# MD_20w.net
KiCad netlist of a schematic drawn in EAGLE
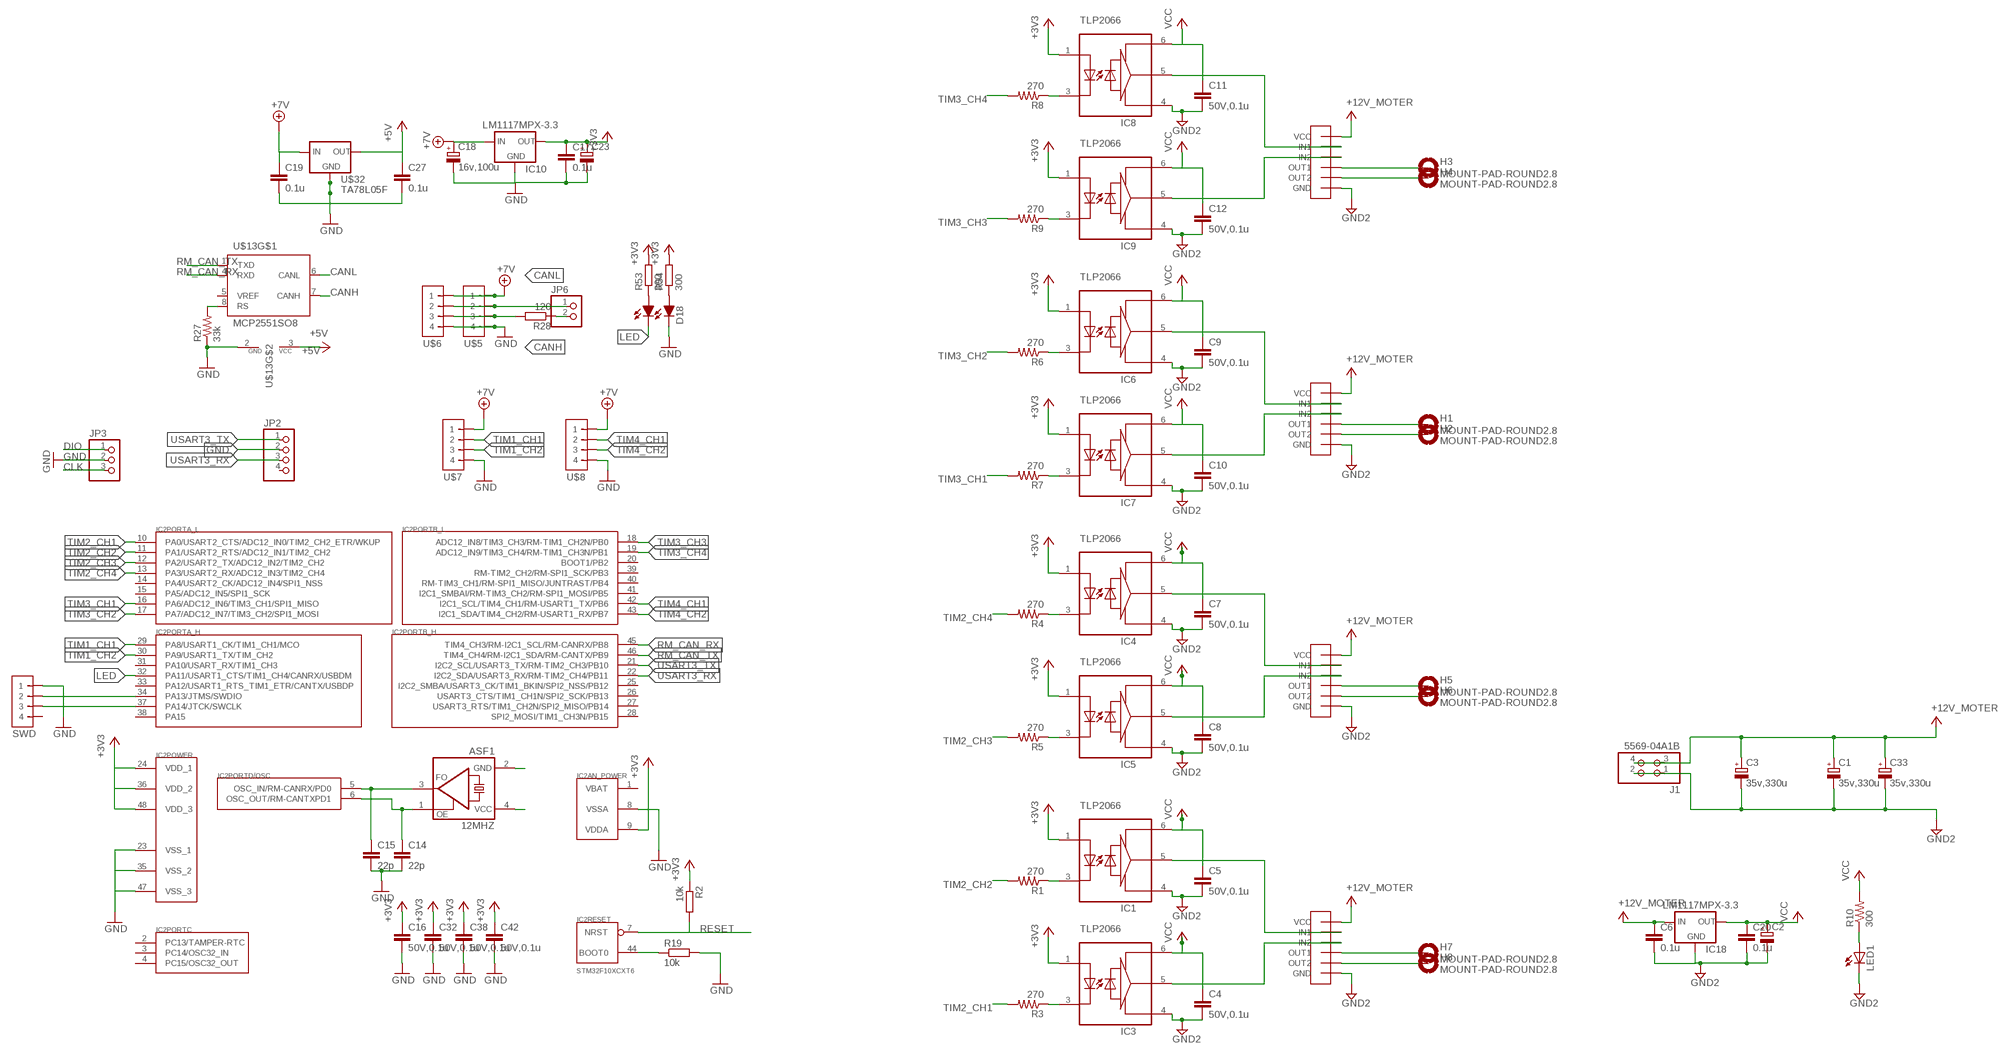
[diagram p0: schematic, sheet 1]

(export (version "E")
  (design (tool "Eeschema 10.0.6"))
  (components
    (comp (ref "12MHZ")
      (value "ASF1")
      (footprint "eagle-import:ASF")
      (libsource (lib "eagle-import") (part "ASF1"))
    )
    (comp (ref "C1")
      (value "35v,330u")
      (footprint "eagle-import:153CLV-1010")
      (libsource (lib "eagle-import") (part "CPOL-EU153CLV-1010"))
    )
    (comp (ref "C2")
      (value "CPOL-EU153CLV-0505")
      (footprint "eagle-import:153CLV-0505")
      (libsource (lib "eagle-import") (part "CPOL-EU153CLV-0505"))
    )
    (comp (ref "C3")
      (value "35v,330u")
      (footprint "eagle-import:153CLV-1010")
      (libsource (lib "eagle-import") (part "CPOL-EU153CLV-1010"))
    )
    (comp (ref "C4")
      (value "50V,0.1u")
      (footprint "eagle-import:C0603")
      (libsource (lib "eagle-import") (part "C-EUC0603"))
    )
    (comp (ref "C5")
      (value "50V,0.1u")
      (footprint "eagle-import:C0603")
      (libsource (lib "eagle-import") (part "C-EUC0603"))
    )
    (comp (ref "C6")
      (value "0.1u")
      (footprint "eagle-import:C0603")
      (libsource (lib "eagle-import") (part "C-EUC0603"))
    )
    (comp (ref "C7")
      (value "50V,0.1u")
      (footprint "eagle-import:C0603")
      (libsource (lib "eagle-import") (part "C-EUC0603"))
    )
    (comp (ref "C8")
      (value "50V,0.1u")
      (footprint "eagle-import:C0603")
      (libsource (lib "eagle-import") (part "C-EUC0603"))
    )
    (comp (ref "C9")
      (value "50V,0.1u")
      (footprint "eagle-import:C0603")
      (libsource (lib "eagle-import") (part "C-EUC0603"))
    )
    (comp (ref "C10")
      (value "50V,0.1u")
      (footprint "eagle-import:C0603")
      (libsource (lib "eagle-import") (part "C-EUC0603"))
    )
    (comp (ref "C11")
      (value "50V,0.1u")
      (footprint "eagle-import:C0603")
      (libsource (lib "eagle-import") (part "C-EUC0603"))
    )
    (comp (ref "C12")
      (value "50V,0.1u")
      (footprint "eagle-import:C0603")
      (libsource (lib "eagle-import") (part "C-EUC0603"))
    )
    (comp (ref "C14")
      (value "22p")
      (footprint "eagle-import:C0603")
      (libsource (lib "eagle-import") (part "C-EUC0603"))
    )
    (comp (ref "C15")
      (value "22p")
      (footprint "eagle-import:C0603")
      (libsource (lib "eagle-import") (part "C-EUC0603"))
    )
    (comp (ref "C16")
      (value "50V,0.1u")
      (footprint "eagle-import:C0603K")
      (libsource (lib "eagle-import") (part "resistor_C-EUC0603K"))
    )
    (comp (ref "C17")
      (value "0.1u")
      (footprint "eagle-import:C0603K")
      (libsource (lib "eagle-import") (part "resistor_C-EUC0603K"))
    )
    (comp (ref "C18")
      (value "16v,100u")
      (footprint "eagle-import:153CLV-0605")
      (libsource (lib "eagle-import") (part "CPOL-EU153CLV-0605"))
    )
    (comp (ref "C19")
      (value "0.1u")
      (footprint "eagle-import:C0603")
      (libsource (lib "eagle-import") (part "C-EUC0603"))
    )
    (comp (ref "C20")
      (value "0.1u")
      (footprint "eagle-import:C0603K")
      (libsource (lib "eagle-import") (part "resistor_C-EUC0603K"))
    )
    (comp (ref "C23")
      (value "CPOL-EU153CLV-0505")
      (footprint "eagle-import:153CLV-0505")
      (libsource (lib "eagle-import") (part "CPOL-EU153CLV-0505"))
    )
    (comp (ref "C27")
      (value "0.1u")
      (footprint "eagle-import:C0603")
      (libsource (lib "eagle-import") (part "C-EUC0603"))
    )
    (comp (ref "C32")
      (value "50V,0.1u")
      (footprint "eagle-import:C0603K")
      (libsource (lib "eagle-import") (part "resistor_C-EUC0603K"))
    )
    (comp (ref "C33")
      (value "35v,330u")
      (footprint "eagle-import:153CLV-1010")
      (libsource (lib "eagle-import") (part "CPOL-EU153CLV-1010"))
    )
    (comp (ref "C38")
      (value "50V,0.1u")
      (footprint "eagle-import:C0603K")
      (libsource (lib "eagle-import") (part "resistor_C-EUC0603K"))
    )
    (comp (ref "C42")
      (value "50V,0.1u")
      (footprint "eagle-import:C0603K")
      (libsource (lib "eagle-import") (part "resistor_C-EUC0603K"))
    )
    (comp (ref "D18")
      (value "SEC2XX4")
      (footprint "eagle-import:LED3025")
      (libsource (lib "eagle-import") (part "SEC2XX4"))
    )
    (comp (ref "H1")
      (value "MOUNT-PAD-ROUND2.8")
      (footprint "eagle-import:2,8-PAD")
      (libsource (lib "eagle-import") (part "MOUNT-PAD-ROUND2.8"))
    )
    (comp (ref "H2")
      (value "MOUNT-PAD-ROUND2.8")
      (footprint "eagle-import:2,8-PAD")
      (libsource (lib "eagle-import") (part "MOUNT-PAD-ROUND2.8"))
    )
    (comp (ref "H3")
      (value "MOUNT-PAD-ROUND2.8")
      (footprint "eagle-import:2,8-PAD")
      (libsource (lib "eagle-import") (part "MOUNT-PAD-ROUND2.8"))
    )
    (comp (ref "H4")
      (value "MOUNT-PAD-ROUND2.8")
      (footprint "eagle-import:2,8-PAD")
      (libsource (lib "eagle-import") (part "MOUNT-PAD-ROUND2.8"))
    )
    (comp (ref "H5")
      (value "MOUNT-PAD-ROUND2.8")
      (footprint "eagle-import:2,8-PAD")
      (libsource (lib "eagle-import") (part "MOUNT-PAD-ROUND2.8"))
    )
    (comp (ref "H6")
      (value "MOUNT-PAD-ROUND2.8")
      (footprint "eagle-import:2,8-PAD")
      (libsource (lib "eagle-import") (part "MOUNT-PAD-ROUND2.8"))
    )
    (comp (ref "H7")
      (value "MOUNT-PAD-ROUND2.8")
      (footprint "eagle-import:2,8-PAD")
      (libsource (lib "eagle-import") (part "MOUNT-PAD-ROUND2.8"))
    )
    (comp (ref "H8")
      (value "MOUNT-PAD-ROUND2.8")
      (footprint "eagle-import:2,8-PAD")
      (libsource (lib "eagle-import") (part "MOUNT-PAD-ROUND2.8"))
    )
    (comp (ref "IC1")
      (value "TLP2066")
      (footprint "eagle-import:MFSOP6")
      (libsource (lib "eagle-import") (part "TLP117"))
    )
    (comp (ref "IC2")
      (value "STM32F10XCXT6")
      (footprint "eagle-import:TQFP48")
      (libsource (lib "eagle-import") (part "STM32F10XCXT6"))
    )
    (comp (ref "IC3")
      (value "TLP2066")
      (footprint "eagle-import:MFSOP6")
      (libsource (lib "eagle-import") (part "TLP117"))
    )
    (comp (ref "IC4")
      (value "TLP2066")
      (footprint "eagle-import:MFSOP6")
      (libsource (lib "eagle-import") (part "TLP117"))
    )
    (comp (ref "IC5")
      (value "TLP2066")
      (footprint "eagle-import:MFSOP6")
      (libsource (lib "eagle-import") (part "TLP117"))
    )
    (comp (ref "IC6")
      (value "TLP2066")
      (footprint "eagle-import:MFSOP6")
      (libsource (lib "eagle-import") (part "TLP117"))
    )
    (comp (ref "IC7")
      (value "TLP2066")
      (footprint "eagle-import:MFSOP6")
      (libsource (lib "eagle-import") (part "TLP117"))
    )
    (comp (ref "IC8")
      (value "TLP2066")
      (footprint "eagle-import:MFSOP6")
      (libsource (lib "eagle-import") (part "TLP117"))
    )
    (comp (ref "IC9")
      (value "TLP2066")
      (footprint "eagle-import:MFSOP6")
      (libsource (lib "eagle-import") (part "TLP117"))
    )
    (comp (ref "IC10")
      (value "LM1117MPX-3.3")
      (footprint "eagle-import:SOT223")
      (libsource (lib "eagle-import") (part "LM1117"))
    )
    (comp (ref "IC18")
      (value "LM1117MPX-3.3")
      (footprint "eagle-import:SOT223")
      (libsource (lib "eagle-import") (part "LM1117"))
    )
    (comp (ref "J1")
      (value "5569-04A1B")
      (footprint "eagle-import:5569-04A1_2")
      (libsource (lib "eagle-import") (part "5569-04A1B"))
    )
    (comp (ref "JP2")
      (value "PINHD-1X4")
      (footprint "eagle-import:1X04")
      (libsource (lib "eagle-import") (part "PINHD-1X4"))
    )
    (comp (ref "JP3")
      (value "PINHD-1X3/90")
      (footprint "eagle-import:1X03_90")
      (libsource (lib "eagle-import") (part "PINHD-1X3/90"))
    )
    (comp (ref "JP6")
      (value "PINHD-1X2")
      (footprint "eagle-import:1X02")
      (libsource (lib "eagle-import") (part "PINHD-1X2"))
    )
    (comp (ref "LED1")
      (value "LEDCHIPLED_1206")
      (footprint "eagle-import:CHIPLED_1206")
      (libsource (lib "eagle-import") (part "LEDCHIPLED_1206"))
    )
    (comp (ref "R1")
      (value "270")
      (footprint "eagle-import:R0603")
      (libsource (lib "eagle-import") (part "resistor_R-US_R0603"))
    )
    (comp (ref "R2")
      (value "10k")
      (footprint "eagle-import:R0603")
      (libsource (lib "eagle-import") (part "R-EU_R0603"))
    )
    (comp (ref "R3")
      (value "270")
      (footprint "eagle-import:R0603")
      (libsource (lib "eagle-import") (part "resistor_R-US_R0603"))
    )
    (comp (ref "R4")
      (value "270")
      (footprint "eagle-import:R0603")
      (libsource (lib "eagle-import") (part "resistor_R-US_R0603"))
    )
    (comp (ref "R5")
      (value "270")
      (footprint "eagle-import:R0603")
      (libsource (lib "eagle-import") (part "resistor_R-US_R0603"))
    )
    (comp (ref "R6")
      (value "270")
      (footprint "eagle-import:R0603")
      (libsource (lib "eagle-import") (part "resistor_R-US_R0603"))
    )
    (comp (ref "R7")
      (value "270")
      (footprint "eagle-import:R0603")
      (libsource (lib "eagle-import") (part "resistor_R-US_R0603"))
    )
    (comp (ref "R8")
      (value "270")
      (footprint "eagle-import:R0603")
      (libsource (lib "eagle-import") (part "resistor_R-US_R0603"))
    )
    (comp (ref "R9")
      (value "270")
      (footprint "eagle-import:R0603")
      (libsource (lib "eagle-import") (part "resistor_R-US_R0603"))
    )
    (comp (ref "R10")
      (value "300")
      (footprint "eagle-import:M2012")
      (libsource (lib "eagle-import") (part "R-US_M2012"))
    )
    (comp (ref "R19")
      (value "10k")
      (footprint "eagle-import:R0603")
      (libsource (lib "eagle-import") (part "R-EU_R0603"))
    )
    (comp (ref "R27")
      (value "33k")
      (footprint "eagle-import:R0603")
      (libsource (lib "eagle-import") (part "resistor_R-US_R0603"))
    )
    (comp (ref "R28")
      (value "120")
      (footprint "eagle-import:R0603")
      (libsource (lib "eagle-import") (part "resistor_R-EU_R0603"))
    )
    (comp (ref "R53")
      (value "300")
      (footprint "eagle-import:R0603")
      (libsource (lib "eagle-import") (part "resistor_R-EU_R0603"))
    )
    (comp (ref "R54")
      (value "300")
      (footprint "eagle-import:R0603")
      (libsource (lib "eagle-import") (part "resistor_R-EU_R0603"))
    )
    (comp (ref "SWD")
      (value "TOP_TYPE_4PIN")
      (footprint "eagle-import:TOP_TYPE_4PIN")
      (libsource (lib "eagle-import") (part "TOP_TYPE_4PIN"))
    )
    (comp (ref "U$1")
      (value "TB6643")
      (footprint "eagle-import:TB6643")
      (libsource (lib "eagle-import") (part "TB6643"))
    )
    (comp (ref "U$2")
      (value "TB6643")
      (footprint "eagle-import:TB6643")
      (libsource (lib "eagle-import") (part "TB6643"))
    )
    (comp (ref "U$3")
      (value "TB6643")
      (footprint "eagle-import:TB6643")
      (libsource (lib "eagle-import") (part "TB6643"))
    )
    (comp (ref "U$4")
      (value "TB6643")
      (footprint "eagle-import:TB6643")
      (libsource (lib "eagle-import") (part "TB6643"))
    )
    (comp (ref "U$5")
      (value "S4B-XH-SM4-TB")
      (footprint "eagle-import:S4B-XH-SM4-TB")
      (libsource (lib "eagle-import") (part "S4B-XH-SM4-TB"))
    )
    (comp (ref "U$6")
      (value "S4B-XH-SM4-TB")
      (footprint "eagle-import:S4B-XH-SM4-TB")
      (libsource (lib "eagle-import") (part "S4B-XH-SM4-TB"))
    )
    (comp (ref "U$7")
      (value "S4B-XH-SM4-TB")
      (footprint "eagle-import:S4B-XH-SM4-TB")
      (libsource (lib "eagle-import") (part "S4B-XH-SM4-TB"))
    )
    (comp (ref "U$8")
      (value "S4B-XH-SM4-TB")
      (footprint "eagle-import:S4B-XH-SM4-TB")
      (libsource (lib "eagle-import") (part "S4B-XH-SM4-TB"))
    )
    (comp (ref "U$13")
      (value "MCP2551SO8")
      (footprint "eagle-import:SO08")
      (libsource (lib "eagle-import") (part "MCP2551SO8"))
    )
    (comp (ref "U$32")
      (value "TA78L05F")
      (footprint "eagle-import:SOT89")
      (libsource (lib "eagle-import") (part "TA78L05F"))
    )
  )
  (nets
    (net (code "1") (name "+3V3") (class "Default")
      (node (ref "C16") (pin "1") (pinfunction "1_1") (pintype "passive"))
      (node (ref "C17") (pin "1") (pinfunction "1_1") (pintype "passive"))
      (node (ref "C23") (pin "+") (pinfunction "+_+") (pintype "passive"))
      (node (ref "C32") (pin "1") (pinfunction "1_1") (pintype "passive"))
      (node (ref "C38") (pin "1") (pinfunction "1_1") (pintype "passive"))
      (node (ref "C42") (pin "1") (pinfunction "1_1") (pintype "passive"))
      (node (ref "IC1") (pin "1") (pinfunction "1_1") (pintype "input"))
      (node (ref "IC10") (pin "2") (pinfunction "OUT1_2") (pintype "passive"))
      (node (ref "IC10") (pin "4") (pinfunction "OUT_4") (pintype "passive"))
      (node (ref "IC2") (pin "24") (pinfunction "VDD_1_24") (pintype "power_in"))
      (node (ref "IC2") (pin "36") (pinfunction "VDD_2_36") (pintype "power_in"))
      (node (ref "IC2") (pin "48") (pinfunction "VDD_3_48") (pintype "power_in"))
      (node (ref "IC2") (pin "9") (pinfunction "VDDA_9") (pintype "power_in"))
      (node (ref "IC3") (pin "1") (pinfunction "1_1") (pintype "input"))
      (node (ref "IC4") (pin "1") (pinfunction "1_1") (pintype "input"))
      (node (ref "IC5") (pin "1") (pinfunction "1_1") (pintype "input"))
      (node (ref "IC6") (pin "1") (pinfunction "1_1") (pintype "input"))
      (node (ref "IC7") (pin "1") (pinfunction "1_1") (pintype "input"))
      (node (ref "IC8") (pin "1") (pinfunction "1_1") (pintype "input"))
      (node (ref "IC9") (pin "1") (pinfunction "1_1") (pintype "input"))
      (node (ref "R2") (pin "1") (pinfunction "1_1") (pintype "passive"))
      (node (ref "R53") (pin "2") (pinfunction "2_2") (pintype "passive"))
      (node (ref "R54") (pin "2") (pinfunction "2_2") (pintype "passive"))
    )
    (net (code "2") (name "+5V") (class "Default")
      (node (ref "C27") (pin "1") (pinfunction "1_1") (pintype "passive"))
      (node (ref "U$13") (pin "3") (pinfunction "VCC_3") (pintype "power_in"))
      (node (ref "U$32") (pin "1") (pinfunction "OUT_1") (pintype "passive"))
    )
    (net (code "3") (name "+7V") (class "Default")
      (node (ref "C18") (pin "+") (pinfunction "+_+") (pintype "passive"))
      (node (ref "C19") (pin "1") (pinfunction "1_1") (pintype "passive"))
      (node (ref "IC10") (pin "3") (pinfunction "IN_3") (pintype "input"))
      (node (ref "U$32") (pin "3") (pinfunction "IN_3") (pintype "input"))
      (node (ref "U$5") (pin "1") (pinfunction "1_1") (pintype "passive"))
      (node (ref "U$6") (pin "1") (pinfunction "1_1") (pintype "passive"))
      (node (ref "U$7") (pin "1") (pinfunction "1_1") (pintype "passive"))
      (node (ref "U$8") (pin "1") (pinfunction "1_1") (pintype "passive"))
    )
    (net (code "4") (name "+12V_MOTER") (class "Default")
      (node (ref "C1") (pin "+") (pinfunction "+_+") (pintype "passive"))
      (node (ref "C3") (pin "+") (pinfunction "+_+") (pintype "passive"))
      (node (ref "C33") (pin "+") (pinfunction "+_+") (pintype "passive"))
      (node (ref "C6") (pin "1") (pinfunction "1_1") (pintype "passive"))
      (node (ref "IC18") (pin "3") (pinfunction "IN_3") (pintype "input"))
      (node (ref "J1") (pin "3") (pinfunction "3_3") (pintype "passive"))
      (node (ref "J1") (pin "4") (pinfunction "4_4") (pintype "passive"))
      (node (ref "U$1") (pin "VCC") (pinfunction "VCC_VCC") (pintype "bidirectional"))
      (node (ref "U$2") (pin "VCC") (pinfunction "VCC_VCC") (pintype "bidirectional"))
      (node (ref "U$3") (pin "VCC") (pinfunction "VCC_VCC") (pintype "bidirectional"))
      (node (ref "U$4") (pin "VCC") (pinfunction "VCC_VCC") (pintype "bidirectional"))
    )
    (net (code "5") (name "/CLK") (class "Default")
      (node (ref "IC2") (pin "37") (pinfunction "PA14/JTCK/SWCLK_37") (pintype "bidirectional"))
      (node (ref "JP3") (pin "3") (pinfunction "3_3") (pintype "passive"))
      (node (ref "SWD") (pin "3") (pinfunction "3_3") (pintype "passive"))
    )
    (net (code "6") (name "/DIO") (class "Default")
      (node (ref "IC2") (pin "34") (pinfunction "PA13/JTMS/SWDIO_34") (pintype "bidirectional"))
      (node (ref "JP3") (pin "1") (pinfunction "1_1") (pintype "passive"))
      (node (ref "SWD") (pin "2") (pinfunction "2_2") (pintype "passive"))
    )
    (net (code "7") (name "/RESET") (class "Default")
      (node (ref "IC2") (pin "7") (pinfunction "NRST_7") (pintype "input"))
      (node (ref "R2") (pin "2") (pinfunction "2_2") (pintype "passive"))
    )
    (net (code "8") (name "/VBAT") (class "Default")
      (node (ref "IC2") (pin "1") (pinfunction "VBAT_1") (pintype "power_in"))
    )
    (net (code "9") (name "CANH") (class "Default")
      (node (ref "R28") (pin "2") (pinfunction "2_2") (pintype "passive"))
      (node (ref "U$13") (pin "7") (pinfunction "CANH_7") (pintype "bidirectional"))
      (node (ref "U$5") (pin "3") (pinfunction "3_3") (pintype "passive"))
      (node (ref "U$6") (pin "3") (pinfunction "3_3") (pintype "passive"))
    )
    (net (code "10") (name "CANL") (class "Default")
      (node (ref "JP6") (pin "1") (pinfunction "1_1") (pintype "passive"))
      (node (ref "U$13") (pin "6") (pinfunction "CANL_6") (pintype "bidirectional"))
      (node (ref "U$5") (pin "2") (pinfunction "2_2") (pintype "passive"))
      (node (ref "U$6") (pin "2") (pinfunction "2_2") (pintype "passive"))
    )
    (net (code "11") (name "GND") (class "Default")
      (node (ref "C14") (pin "2") (pinfunction "2_2") (pintype "passive"))
      (node (ref "C15") (pin "2") (pinfunction "2_2") (pintype "passive"))
      (node (ref "C16") (pin "2") (pinfunction "2_2") (pintype "passive"))
      (node (ref "C17") (pin "2") (pinfunction "2_2") (pintype "passive"))
      (node (ref "C18") (pin "-") (pinfunction "-_-") (pintype "passive"))
      (node (ref "C19") (pin "2") (pinfunction "2_2") (pintype "passive"))
      (node (ref "C23") (pin "-") (pinfunction "-_-") (pintype "passive"))
      (node (ref "C27") (pin "2") (pinfunction "2_2") (pintype "passive"))
      (node (ref "C32") (pin "2") (pinfunction "2_2") (pintype "passive"))
      (node (ref "C38") (pin "2") (pinfunction "2_2") (pintype "passive"))
      (node (ref "C42") (pin "2") (pinfunction "2_2") (pintype "passive"))
      (node (ref "D18") (pin "1") (pinfunction "C0_1") (pintype "passive"))
      (node (ref "IC10") (pin "1") (pinfunction "GND_1") (pintype "input"))
      (node (ref "IC2") (pin "23") (pinfunction "VSS_1_23") (pintype "power_in"))
      (node (ref "IC2") (pin "35") (pinfunction "VSS_2_35") (pintype "power_in"))
      (node (ref "IC2") (pin "47") (pinfunction "VSS_3_47") (pintype "power_in"))
      (node (ref "IC2") (pin "8") (pinfunction "VSSA_8") (pintype "power_in"))
      (node (ref "JP2") (pin "2") (pinfunction "2_2") (pintype "passive"))
      (node (ref "JP3") (pin "2") (pinfunction "2_2") (pintype "passive"))
      (node (ref "R19") (pin "2") (pinfunction "2_2") (pintype "passive"))
      (node (ref "R27") (pin "1") (pinfunction "1_1") (pintype "passive"))
      (node (ref "SWD") (pin "1") (pinfunction "1_1") (pintype "passive"))
      (node (ref "U$13") (pin "2") (pinfunction "GND_2") (pintype "power_in"))
      (node (ref "U$32") (pin "2") (pinfunction "GND_2") (pintype "input"))
      (node (ref "U$32") (pin "2@1") (pinfunction "GND1_2@1") (pintype "input"))
      (node (ref "U$5") (pin "4") (pinfunction "4_4") (pintype "passive"))
      (node (ref "U$6") (pin "4") (pinfunction "4_4") (pintype "passive"))
      (node (ref "U$7") (pin "4") (pinfunction "4_4") (pintype "passive"))
      (node (ref "U$8") (pin "4") (pinfunction "4_4") (pintype "passive"))
    )
    (net (code "12") (name "GND2") (class "Default")
      (node (ref "C1") (pin "-") (pinfunction "-_-") (pintype "passive"))
      (node (ref "C10") (pin "2") (pinfunction "2_2") (pintype "passive"))
      (node (ref "C11") (pin "2") (pinfunction "2_2") (pintype "passive"))
      (node (ref "C12") (pin "2") (pinfunction "2_2") (pintype "passive"))
      (node (ref "C2") (pin "-") (pinfunction "-_-") (pintype "passive"))
      (node (ref "C20") (pin "2") (pinfunction "2_2") (pintype "passive"))
      (node (ref "C3") (pin "-") (pinfunction "-_-") (pintype "passive"))
      (node (ref "C33") (pin "-") (pinfunction "-_-") (pintype "passive"))
      (node (ref "C4") (pin "2") (pinfunction "2_2") (pintype "passive"))
      (node (ref "C5") (pin "2") (pinfunction "2_2") (pintype "passive"))
      (node (ref "C6") (pin "2") (pinfunction "2_2") (pintype "passive"))
      (node (ref "C7") (pin "2") (pinfunction "2_2") (pintype "passive"))
      (node (ref "C8") (pin "2") (pinfunction "2_2") (pintype "passive"))
      (node (ref "C9") (pin "2") (pinfunction "2_2") (pintype "passive"))
      (node (ref "IC1") (pin "4") (pinfunction "GND_4") (pintype "power_in"))
      (node (ref "IC18") (pin "1") (pinfunction "GND_1") (pintype "input"))
      (node (ref "IC3") (pin "4") (pinfunction "GND_4") (pintype "power_in"))
      (node (ref "IC4") (pin "4") (pinfunction "GND_4") (pintype "power_in"))
      (node (ref "IC5") (pin "4") (pinfunction "GND_4") (pintype "power_in"))
      (node (ref "IC6") (pin "4") (pinfunction "GND_4") (pintype "power_in"))
      (node (ref "IC7") (pin "4") (pinfunction "GND_4") (pintype "power_in"))
      (node (ref "IC8") (pin "4") (pinfunction "GND_4") (pintype "power_in"))
      (node (ref "IC9") (pin "4") (pinfunction "GND_4") (pintype "power_in"))
      (node (ref "J1") (pin "1") (pinfunction "1_1") (pintype "passive"))
      (node (ref "J1") (pin "2") (pinfunction "2_2") (pintype "passive"))
      (node (ref "LED1") (pin "C") (pinfunction "C_C") (pintype "passive"))
      (node (ref "U$1") (pin "GND") (pinfunction "GND_GND") (pintype "bidirectional"))
      (node (ref "U$2") (pin "GND") (pinfunction "GND_GND") (pintype "bidirectional"))
      (node (ref "U$3") (pin "GND") (pinfunction "GND_GND") (pintype "bidirectional"))
      (node (ref "U$4") (pin "GND") (pinfunction "GND_GND") (pintype "bidirectional"))
    )
    (net (code "13") (name "LED") (class "Default")
      (node (ref "D18") (pin "2") (pinfunction "C1_2") (pintype "passive"))
      (node (ref "IC2") (pin "32") (pinfunction "PA11/USART1_CTS/TIM1_CH4/CANRX/USBDM_32") (pintype "bidirectional"))
    )
    (net (code "14") (name "Net-(12MHZ-FO)") (class "Default")
      (node (ref "12MHZ") (pin "3") (pinfunction "FO_3") (pintype "output"))
      (node (ref "C15") (pin "1") (pinfunction "1_1") (pintype "passive"))
      (node (ref "IC2") (pin "5") (pinfunction "OSC_IN/RM-CANRX/PD0_5") (pintype "bidirectional"))
    )
    (net (code "15") (name "Net-(12MHZ-OE)") (class "Default")
      (node (ref "12MHZ") (pin "1") (pinfunction "OE_1") (pintype "input"))
      (node (ref "C14") (pin "1") (pinfunction "1_1") (pintype "passive"))
      (node (ref "IC2") (pin "6") (pinfunction "OSC_OUT/RM-CANTXPD1_6") (pintype "bidirectional"))
    )
    (net (code "16") (name "Net-(D18-A0)") (class "Default")
      (node (ref "D18") (pin "4") (pinfunction "A0_4") (pintype "passive"))
      (node (ref "R54") (pin "1") (pinfunction "1_1") (pintype "passive"))
    )
    (net (code "17") (name "Net-(D18-A1)") (class "Default")
      (node (ref "D18") (pin "3") (pinfunction "A1_3") (pintype "passive"))
      (node (ref "R53") (pin "1") (pinfunction "1_1") (pintype "passive"))
    )
    (net (code "18") (name "Net-(H1-MOUNT)") (class "Default")
      (node (ref "H1") (pin "B2,8") (pinfunction "MOUNT_B2,8") (pintype "passive"))
      (node (ref "U$3") (pin "OUT1") (pinfunction "OUT1_OUT1") (pintype "bidirectional"))
    )
    (net (code "19") (name "Net-(H2-MOUNT)") (class "Default")
      (node (ref "H2") (pin "B2,8") (pinfunction "MOUNT_B2,8") (pintype "passive"))
      (node (ref "U$3") (pin "OUT2") (pinfunction "OUT2_OUT2") (pintype "bidirectional"))
    )
    (net (code "20") (name "Net-(H3-MOUNT)") (class "Default")
      (node (ref "H3") (pin "B2,8") (pinfunction "MOUNT_B2,8") (pintype "passive"))
      (node (ref "U$4") (pin "OUT1") (pinfunction "OUT1_OUT1") (pintype "bidirectional"))
    )
    (net (code "21") (name "Net-(H4-MOUNT)") (class "Default")
      (node (ref "H4") (pin "B2,8") (pinfunction "MOUNT_B2,8") (pintype "passive"))
      (node (ref "U$4") (pin "OUT2") (pinfunction "OUT2_OUT2") (pintype "bidirectional"))
    )
    (net (code "22") (name "Net-(H5-MOUNT)") (class "Default")
      (node (ref "H5") (pin "B2,8") (pinfunction "MOUNT_B2,8") (pintype "passive"))
      (node (ref "U$2") (pin "OUT1") (pinfunction "OUT1_OUT1") (pintype "bidirectional"))
    )
    (net (code "23") (name "Net-(H6-MOUNT)") (class "Default")
      (node (ref "H6") (pin "B2,8") (pinfunction "MOUNT_B2,8") (pintype "passive"))
      (node (ref "U$2") (pin "OUT2") (pinfunction "OUT2_OUT2") (pintype "bidirectional"))
    )
    (net (code "24") (name "Net-(H7-MOUNT)") (class "Default")
      (node (ref "H7") (pin "B2,8") (pinfunction "MOUNT_B2,8") (pintype "passive"))
      (node (ref "U$1") (pin "OUT1") (pinfunction "OUT1_OUT1") (pintype "bidirectional"))
    )
    (net (code "25") (name "Net-(H8-MOUNT)") (class "Default")
      (node (ref "H8") (pin "B2,8") (pinfunction "MOUNT_B2,8") (pintype "passive"))
      (node (ref "U$1") (pin "OUT2") (pinfunction "OUT2_OUT2") (pintype "bidirectional"))
    )
    (net (code "26") (name "Net-(IC1-Pad3)") (class "Default")
      (node (ref "IC1") (pin "3") (pinfunction "3_3") (pintype "output"))
      (node (ref "R1") (pin "1") (pinfunction "1_1") (pintype "passive"))
    )
    (net (code "27") (name "Net-(IC1-Pad5)") (class "Default")
      (node (ref "IC1") (pin "5") (pinfunction "5_5") (pintype "output"))
      (node (ref "U$1") (pin "IN1") (pinfunction "IN1_IN1") (pintype "bidirectional"))
    )
    (net (code "28") (name "Net-(IC2I-BOOT0)") (class "Default")
      (node (ref "IC2") (pin "44") (pinfunction "BOOT0_44") (pintype "input"))
      (node (ref "R19") (pin "1") (pinfunction "1_1") (pintype "passive"))
    )
    (net (code "29") (name "Net-(IC3-Pad3)") (class "Default")
      (node (ref "IC3") (pin "3") (pinfunction "3_3") (pintype "output"))
      (node (ref "R3") (pin "1") (pinfunction "1_1") (pintype "passive"))
    )
    (net (code "30") (name "Net-(IC3-Pad5)") (class "Default")
      (node (ref "IC3") (pin "5") (pinfunction "5_5") (pintype "output"))
      (node (ref "U$1") (pin "IN2") (pinfunction "IN2_IN2") (pintype "bidirectional"))
    )
    (net (code "31") (name "Net-(IC4-Pad3)") (class "Default")
      (node (ref "IC4") (pin "3") (pinfunction "3_3") (pintype "output"))
      (node (ref "R4") (pin "1") (pinfunction "1_1") (pintype "passive"))
    )
    (net (code "32") (name "Net-(IC4-Pad5)") (class "Default")
      (node (ref "IC4") (pin "5") (pinfunction "5_5") (pintype "output"))
      (node (ref "U$2") (pin "IN1") (pinfunction "IN1_IN1") (pintype "bidirectional"))
    )
    (net (code "33") (name "Net-(IC5-Pad3)") (class "Default")
      (node (ref "IC5") (pin "3") (pinfunction "3_3") (pintype "output"))
      (node (ref "R5") (pin "1") (pinfunction "1_1") (pintype "passive"))
    )
    (net (code "34") (name "Net-(IC5-Pad5)") (class "Default")
      (node (ref "IC5") (pin "5") (pinfunction "5_5") (pintype "output"))
      (node (ref "U$2") (pin "IN2") (pinfunction "IN2_IN2") (pintype "bidirectional"))
    )
    (net (code "35") (name "Net-(IC6-Pad3)") (class "Default")
      (node (ref "IC6") (pin "3") (pinfunction "3_3") (pintype "output"))
      (node (ref "R6") (pin "1") (pinfunction "1_1") (pintype "passive"))
    )
    (net (code "36") (name "Net-(IC6-Pad5)") (class "Default")
      (node (ref "IC6") (pin "5") (pinfunction "5_5") (pintype "output"))
      (node (ref "U$3") (pin "IN1") (pinfunction "IN1_IN1") (pintype "bidirectional"))
    )
    (net (code "37") (name "Net-(IC7-Pad3)") (class "Default")
      (node (ref "IC7") (pin "3") (pinfunction "3_3") (pintype "output"))
      (node (ref "R7") (pin "1") (pinfunction "1_1") (pintype "passive"))
    )
    (net (code "38") (name "Net-(IC7-Pad5)") (class "Default")
      (node (ref "IC7") (pin "5") (pinfunction "5_5") (pintype "output"))
      (node (ref "U$3") (pin "IN2") (pinfunction "IN2_IN2") (pintype "bidirectional"))
    )
    (net (code "39") (name "Net-(IC8-Pad3)") (class "Default")
      (node (ref "IC8") (pin "3") (pinfunction "3_3") (pintype "output"))
      (node (ref "R8") (pin "1") (pinfunction "1_1") (pintype "passive"))
    )
    (net (code "40") (name "Net-(IC8-Pad5)") (class "Default")
      (node (ref "IC8") (pin "5") (pinfunction "5_5") (pintype "output"))
      (node (ref "U$4") (pin "IN1") (pinfunction "IN1_IN1") (pintype "bidirectional"))
    )
    (net (code "41") (name "Net-(IC9-Pad3)") (class "Default")
      (node (ref "IC9") (pin "3") (pinfunction "3_3") (pintype "output"))
      (node (ref "R9") (pin "1") (pinfunction "1_1") (pintype "passive"))
    )
    (net (code "42") (name "Net-(IC9-Pad5)") (class "Default")
      (node (ref "IC9") (pin "5") (pinfunction "5_5") (pintype "output"))
      (node (ref "U$4") (pin "IN2") (pinfunction "IN2_IN2") (pintype "bidirectional"))
    )
    (net (code "43") (name "Net-(JP6-Pad2)") (class "Default")
      (node (ref "JP6") (pin "2") (pinfunction "2_2") (pintype "passive"))
      (node (ref "R28") (pin "1") (pinfunction "1_1") (pintype "passive"))
    )
    (net (code "44") (name "Net-(LED1-PadA)") (class "Default")
      (node (ref "LED1") (pin "A") (pinfunction "A_A") (pintype "passive"))
      (node (ref "R10") (pin "1") (pinfunction "1_1") (pintype "passive"))
    )
    (net (code "45") (name "Net-(U$13A-RS)") (class "Default")
      (node (ref "R27") (pin "2") (pinfunction "2_2") (pintype "passive"))
      (node (ref "U$13") (pin "8") (pinfunction "RS_8") (pintype "bidirectional"))
    )
    (net (code "46") (name "RM_CAN_RX") (class "Default")
      (node (ref "IC2") (pin "45") (pinfunction "TIM4_CH3/RM-I2C1_SCL/RM-CANRX/PB8_45") (pintype "bidirectional"))
      (node (ref "U$13") (pin "4") (pinfunction "RXD_4") (pintype "bidirectional"))
    )
    (net (code "47") (name "RM_CAN_TX") (class "Default")
      (node (ref "IC2") (pin "46") (pinfunction "TIM4_CH4/RM-I2C1_SDA/RM-CANTX/PB9_46") (pintype "bidirectional"))
      (node (ref "U$13") (pin "1") (pinfunction "TXD_1") (pintype "bidirectional"))
    )
    (net (code "48") (name "TIM1_CH1") (class "Default")
      (node (ref "IC2") (pin "29") (pinfunction "PA8/USART1_CK/TIM1_CH1/MCO_29") (pintype "bidirectional"))
      (node (ref "U$7") (pin "2") (pinfunction "2_2") (pintype "passive"))
    )
    (net (code "49") (name "TIM1_CH2") (class "Default")
      (node (ref "IC2") (pin "30") (pinfunction "PA9/USART1_TX/TIM_CH2_30") (pintype "bidirectional"))
      (node (ref "U$7") (pin "3") (pinfunction "3_3") (pintype "passive"))
    )
    (net (code "50") (name "TIM2_CH1") (class "Default")
      (node (ref "IC2") (pin "10") (pinfunction "PA0/USART2_CTS/ADC12_IN0/TIM2_CH2_ETR/WKUP_10") (pintype "bidirectional"))
      (node (ref "R3") (pin "2") (pinfunction "2_2") (pintype "passive"))
    )
    (net (code "51") (name "TIM2_CH2") (class "Default")
      (node (ref "IC2") (pin "11") (pinfunction "PA1/USART2_RTS/ADC12_IN1/TIM2_CH2_11") (pintype "bidirectional"))
      (node (ref "R1") (pin "2") (pinfunction "2_2") (pintype "passive"))
    )
    (net (code "52") (name "TIM2_CH3") (class "Default")
      (node (ref "IC2") (pin "12") (pinfunction "PA2/USART2_TX/ADC12_IN2/TIM2_CH2_12") (pintype "bidirectional"))
      (node (ref "R5") (pin "2") (pinfunction "2_2") (pintype "passive"))
    )
    (net (code "53") (name "TIM2_CH4") (class "Default")
      (node (ref "IC2") (pin "13") (pinfunction "PA3/USART2_RX/ADC12_IN3/TIM2_CH4_13") (pintype "bidirectional"))
      (node (ref "R4") (pin "2") (pinfunction "2_2") (pintype "passive"))
    )
    (net (code "54") (name "TIM3_CH1") (class "Default")
      (node (ref "IC2") (pin "16") (pinfunction "PA6/ADC12_IN6/TIM3_CH1/SPI1_MISO_16") (pintype "bidirectional"))
      (node (ref "R7") (pin "2") (pinfunction "2_2") (pintype "passive"))
    )
    (net (code "55") (name "TIM3_CH2") (class "Default")
      (node (ref "IC2") (pin "17") (pinfunction "PA7/ADC12_IN7/TIM3_CH2/SPI1_MOSI_17") (pintype "bidirectional"))
      (node (ref "R6") (pin "2") (pinfunction "2_2") (pintype "passive"))
    )
    (net (code "56") (name "TIM3_CH3") (class "Default")
      (node (ref "IC2") (pin "18") (pinfunction "ADC12_IN8/TIM3_CH3/RM-TIM1_CH2N/PB0_18") (pintype "bidirectional"))
      (node (ref "R9") (pin "2") (pinfunction "2_2") (pintype "passive"))
    )
    (net (code "57") (name "TIM3_CH4") (class "Default")
      (node (ref "IC2") (pin "19") (pinfunction "ADC12_IN9/TIM3_CH4/RM-TIM1_CH3N/PB1_19") (pintype "bidirectional"))
      (node (ref "R8") (pin "2") (pinfunction "2_2") (pintype "passive"))
    )
    (net (code "58") (name "TIM4_CH1") (class "Default")
      (node (ref "IC2") (pin "42") (pinfunction "I2C1_SCL/TIM4_CH1/RM-USART1_TX/PB6_42") (pintype "bidirectional"))
      (node (ref "U$8") (pin "2") (pinfunction "2_2") (pintype "passive"))
    )
    (net (code "59") (name "TIM4_CH2") (class "Default")
      (node (ref "IC2") (pin "43") (pinfunction "I2C1_SDA/TIM4_CH2/RM-USART1_RX/PB7_43") (pintype "bidirectional"))
      (node (ref "U$8") (pin "3") (pinfunction "3_3") (pintype "passive"))
    )
    (net (code "60") (name "USART3_RX") (class "Default")
      (node (ref "IC2") (pin "22") (pinfunction "I2C2_SDA/USART3_RX/RM-TIM2_CH4/PB11_22") (pintype "bidirectional"))
      (node (ref "JP2") (pin "3") (pinfunction "3_3") (pintype "passive"))
    )
    (net (code "61") (name "USART3_TX") (class "Default")
      (node (ref "IC2") (pin "21") (pinfunction "I2C2_SCL/USART3_TX/RM-TIM2_CH3/PB10_21") (pintype "bidirectional"))
      (node (ref "JP2") (pin "1") (pinfunction "1_1") (pintype "passive"))
    )
    (net (code "62") (name "VCC") (class "Default")
      (node (ref "C10") (pin "1") (pinfunction "1_1") (pintype "passive"))
      (node (ref "C11") (pin "1") (pinfunction "1_1") (pintype "passive"))
      (node (ref "C12") (pin "1") (pinfunction "1_1") (pintype "passive"))
      (node (ref "C2") (pin "+") (pinfunction "+_+") (pintype "passive"))
      (node (ref "C20") (pin "1") (pinfunction "1_1") (pintype "passive"))
      (node (ref "C4") (pin "1") (pinfunction "1_1") (pintype "passive"))
      (node (ref "C5") (pin "1") (pinfunction "1_1") (pintype "passive"))
      (node (ref "C7") (pin "1") (pinfunction "1_1") (pintype "passive"))
      (node (ref "C8") (pin "1") (pinfunction "1_1") (pintype "passive"))
      (node (ref "C9") (pin "1") (pinfunction "1_1") (pintype "passive"))
      (node (ref "IC1") (pin "6") (pinfunction "VCC_6") (pintype "power_in"))
      (node (ref "IC18") (pin "2") (pinfunction "OUT1_2") (pintype "passive"))
      (node (ref "IC18") (pin "4") (pinfunction "OUT_4") (pintype "passive"))
      (node (ref "IC3") (pin "6") (pinfunction "VCC_6") (pintype "power_in"))
      (node (ref "IC4") (pin "6") (pinfunction "VCC_6") (pintype "power_in"))
      (node (ref "IC5") (pin "6") (pinfunction "VCC_6") (pintype "power_in"))
      (node (ref "IC6") (pin "6") (pinfunction "VCC_6") (pintype "power_in"))
      (node (ref "IC7") (pin "6") (pinfunction "VCC_6") (pintype "power_in"))
      (node (ref "IC8") (pin "6") (pinfunction "VCC_6") (pintype "power_in"))
      (node (ref "IC9") (pin "6") (pinfunction "VCC_6") (pintype "power_in"))
      (node (ref "R10") (pin "2") (pinfunction "2_2") (pintype "passive"))
    )
    (net (code "63") (name "unconnected-(12MHZ-GND-Pad2)") (class "Default")
      (node (ref "12MHZ") (pin "2") (pinfunction "GND_2") (pintype "power_in"))
    )
    (net (code "64") (name "unconnected-(12MHZ-VCC-Pad4)") (class "Default")
      (node (ref "12MHZ") (pin "4") (pinfunction "VCC_4") (pintype "power_in"))
    )
    (net (code "65") (name "unconnected-(IC2B-PA10{slash}USART_RX{slash}TIM1_CH3-Pad31)") (class "Default")
      (node (ref "IC2") (pin "31") (pinfunction "PA10/USART_RX/TIM1_CH3_31") (pintype "bidirectional"))
    )
    (net (code "66") (name "unconnected-(IC2B-PA12{slash}USART1_RTS_TIM1_ETR{slash}CANTX{slash}USBDP-Pad33)") (class "Default")
      (node (ref "IC2") (pin "33") (pinfunction "PA12/USART1_RTS_TIM1_ETR/CANTX/USBDP_33") (pintype "bidirectional"))
    )
    (net (code "67") (name "unconnected-(IC2B-PA15-Pad38)") (class "Default")
      (node (ref "IC2") (pin "38") (pinfunction "PA15_38") (pintype "bidirectional"))
    )
    (net (code "68") (name "unconnected-(IC2C-PA4{slash}USART2_CK{slash}ADC12_IN4{slash}SPI1_NSS-Pad14)") (class "Default")
      (node (ref "IC2") (pin "14") (pinfunction "PA4/USART2_CK/ADC12_IN4/SPI1_NSS_14") (pintype "bidirectional"))
    )
    (net (code "69") (name "unconnected-(IC2C-PA5{slash}ADC12_IN5{slash}SPI1_SCK-Pad15)") (class "Default")
      (node (ref "IC2") (pin "15") (pinfunction "PA5/ADC12_IN5/SPI1_SCK_15") (pintype "bidirectional"))
    )
    (net (code "70") (name "unconnected-(IC2D-I2C2_SMBA{slash}USART3_CK{slash}TIM1_BKIN{slash}SPI2_NSS{slash}PB12-Pad25)") (class "Default")
      (node (ref "IC2") (pin "25") (pinfunction "I2C2_SMBA/USART3_CK/TIM1_BKIN/SPI2_NSS/PB12_25") (pintype "bidirectional"))
    )
    (net (code "71") (name "unconnected-(IC2D-SPI2_MOSI{slash}TIM1_CH3N{slash}PB15-Pad28)") (class "Default")
      (node (ref "IC2") (pin "28") (pinfunction "SPI2_MOSI/TIM1_CH3N/PB15_28") (pintype "bidirectional"))
    )
    (net (code "72") (name "unconnected-(IC2D-USART3_CTS{slash}TIM1_CH1N{slash}SPI2_SCK{slash}PB13-Pad26)") (class "Default")
      (node (ref "IC2") (pin "26") (pinfunction "USART3_CTS/TIM1_CH1N/SPI2_SCK/PB13_26") (pintype "bidirectional"))
    )
    (net (code "73") (name "unconnected-(IC2D-USART3_RTS{slash}TIM1_CH2N{slash}SPI2_MISO{slash}PB14-Pad27)") (class "Default")
      (node (ref "IC2") (pin "27") (pinfunction "USART3_RTS/TIM1_CH2N/SPI2_MISO/PB14_27") (pintype "bidirectional"))
    )
    (net (code "74") (name "unconnected-(IC2E-BOOT1{slash}PB2-Pad20)") (class "Default")
      (node (ref "IC2") (pin "20") (pinfunction "BOOT1/PB2_20") (pintype "bidirectional"))
    )
    (net (code "75") (name "unconnected-(IC2E-I2C1_SMBAI{slash}RM-TIM3_CH2{slash}RM-SPI1_MOSI{slash}PB5-Pad41)") (class "Default")
      (node (ref "IC2") (pin "41") (pinfunction "I2C1_SMBAI/RM-TIM3_CH2/RM-SPI1_MOSI/PB5_41") (pintype "bidirectional"))
    )
    (net (code "76") (name "unconnected-(IC2E-RM-TIM2_CH2{slash}RM-SPI1_SCK{slash}PB3-Pad39)") (class "Default")
      (node (ref "IC2") (pin "39") (pinfunction "RM-TIM2_CH2/RM-SPI1_SCK/PB3_39") (pintype "bidirectional"))
    )
    (net (code "77") (name "unconnected-(IC2E-RM-TIM3_CH1{slash}RM-SPI1_MISO{slash}JUNTRAST{slash}PB4-Pad40)") (class "Default")
      (node (ref "IC2") (pin "40") (pinfunction "RM-TIM3_CH1/RM-SPI1_MISO/JUNTRAST/PB4_40") (pintype "bidirectional"))
    )
    (net (code "78") (name "unconnected-(IC2F-PC13{slash}TAMPER-RTC-Pad2)") (class "Default")
      (node (ref "IC2") (pin "2") (pinfunction "PC13/TAMPER-RTC_2") (pintype "bidirectional"))
    )
    (net (code "79") (name "unconnected-(IC2F-PC14{slash}OSC32_IN-Pad3)") (class "Default")
      (node (ref "IC2") (pin "3") (pinfunction "PC14/OSC32_IN_3") (pintype "bidirectional"))
    )
    (net (code "80") (name "unconnected-(IC2F-PC15{slash}OSC32_OUT-Pad4)") (class "Default")
      (node (ref "IC2") (pin "4") (pinfunction "PC15/OSC32_OUT_4") (pintype "bidirectional"))
    )
    (net (code "81") (name "unconnected-(JP2-Pad4)") (class "Default")
      (node (ref "JP2") (pin "4") (pinfunction "4_4") (pintype "passive"))
    )
    (net (code "82") (name "unconnected-(SWD-Pad4)") (class "Default")
      (node (ref "SWD") (pin "4") (pinfunction "4_4") (pintype "passive"))
    )
    (net (code "83") (name "unconnected-(U$13A-VREF-Pad5)") (class "Default")
      (node (ref "U$13") (pin "5") (pinfunction "VREF_5") (pintype "bidirectional"))
    )
  )
)
